# bird_beaks_2_0.net
KiCad netlist of a schematic drawn in EAGLE
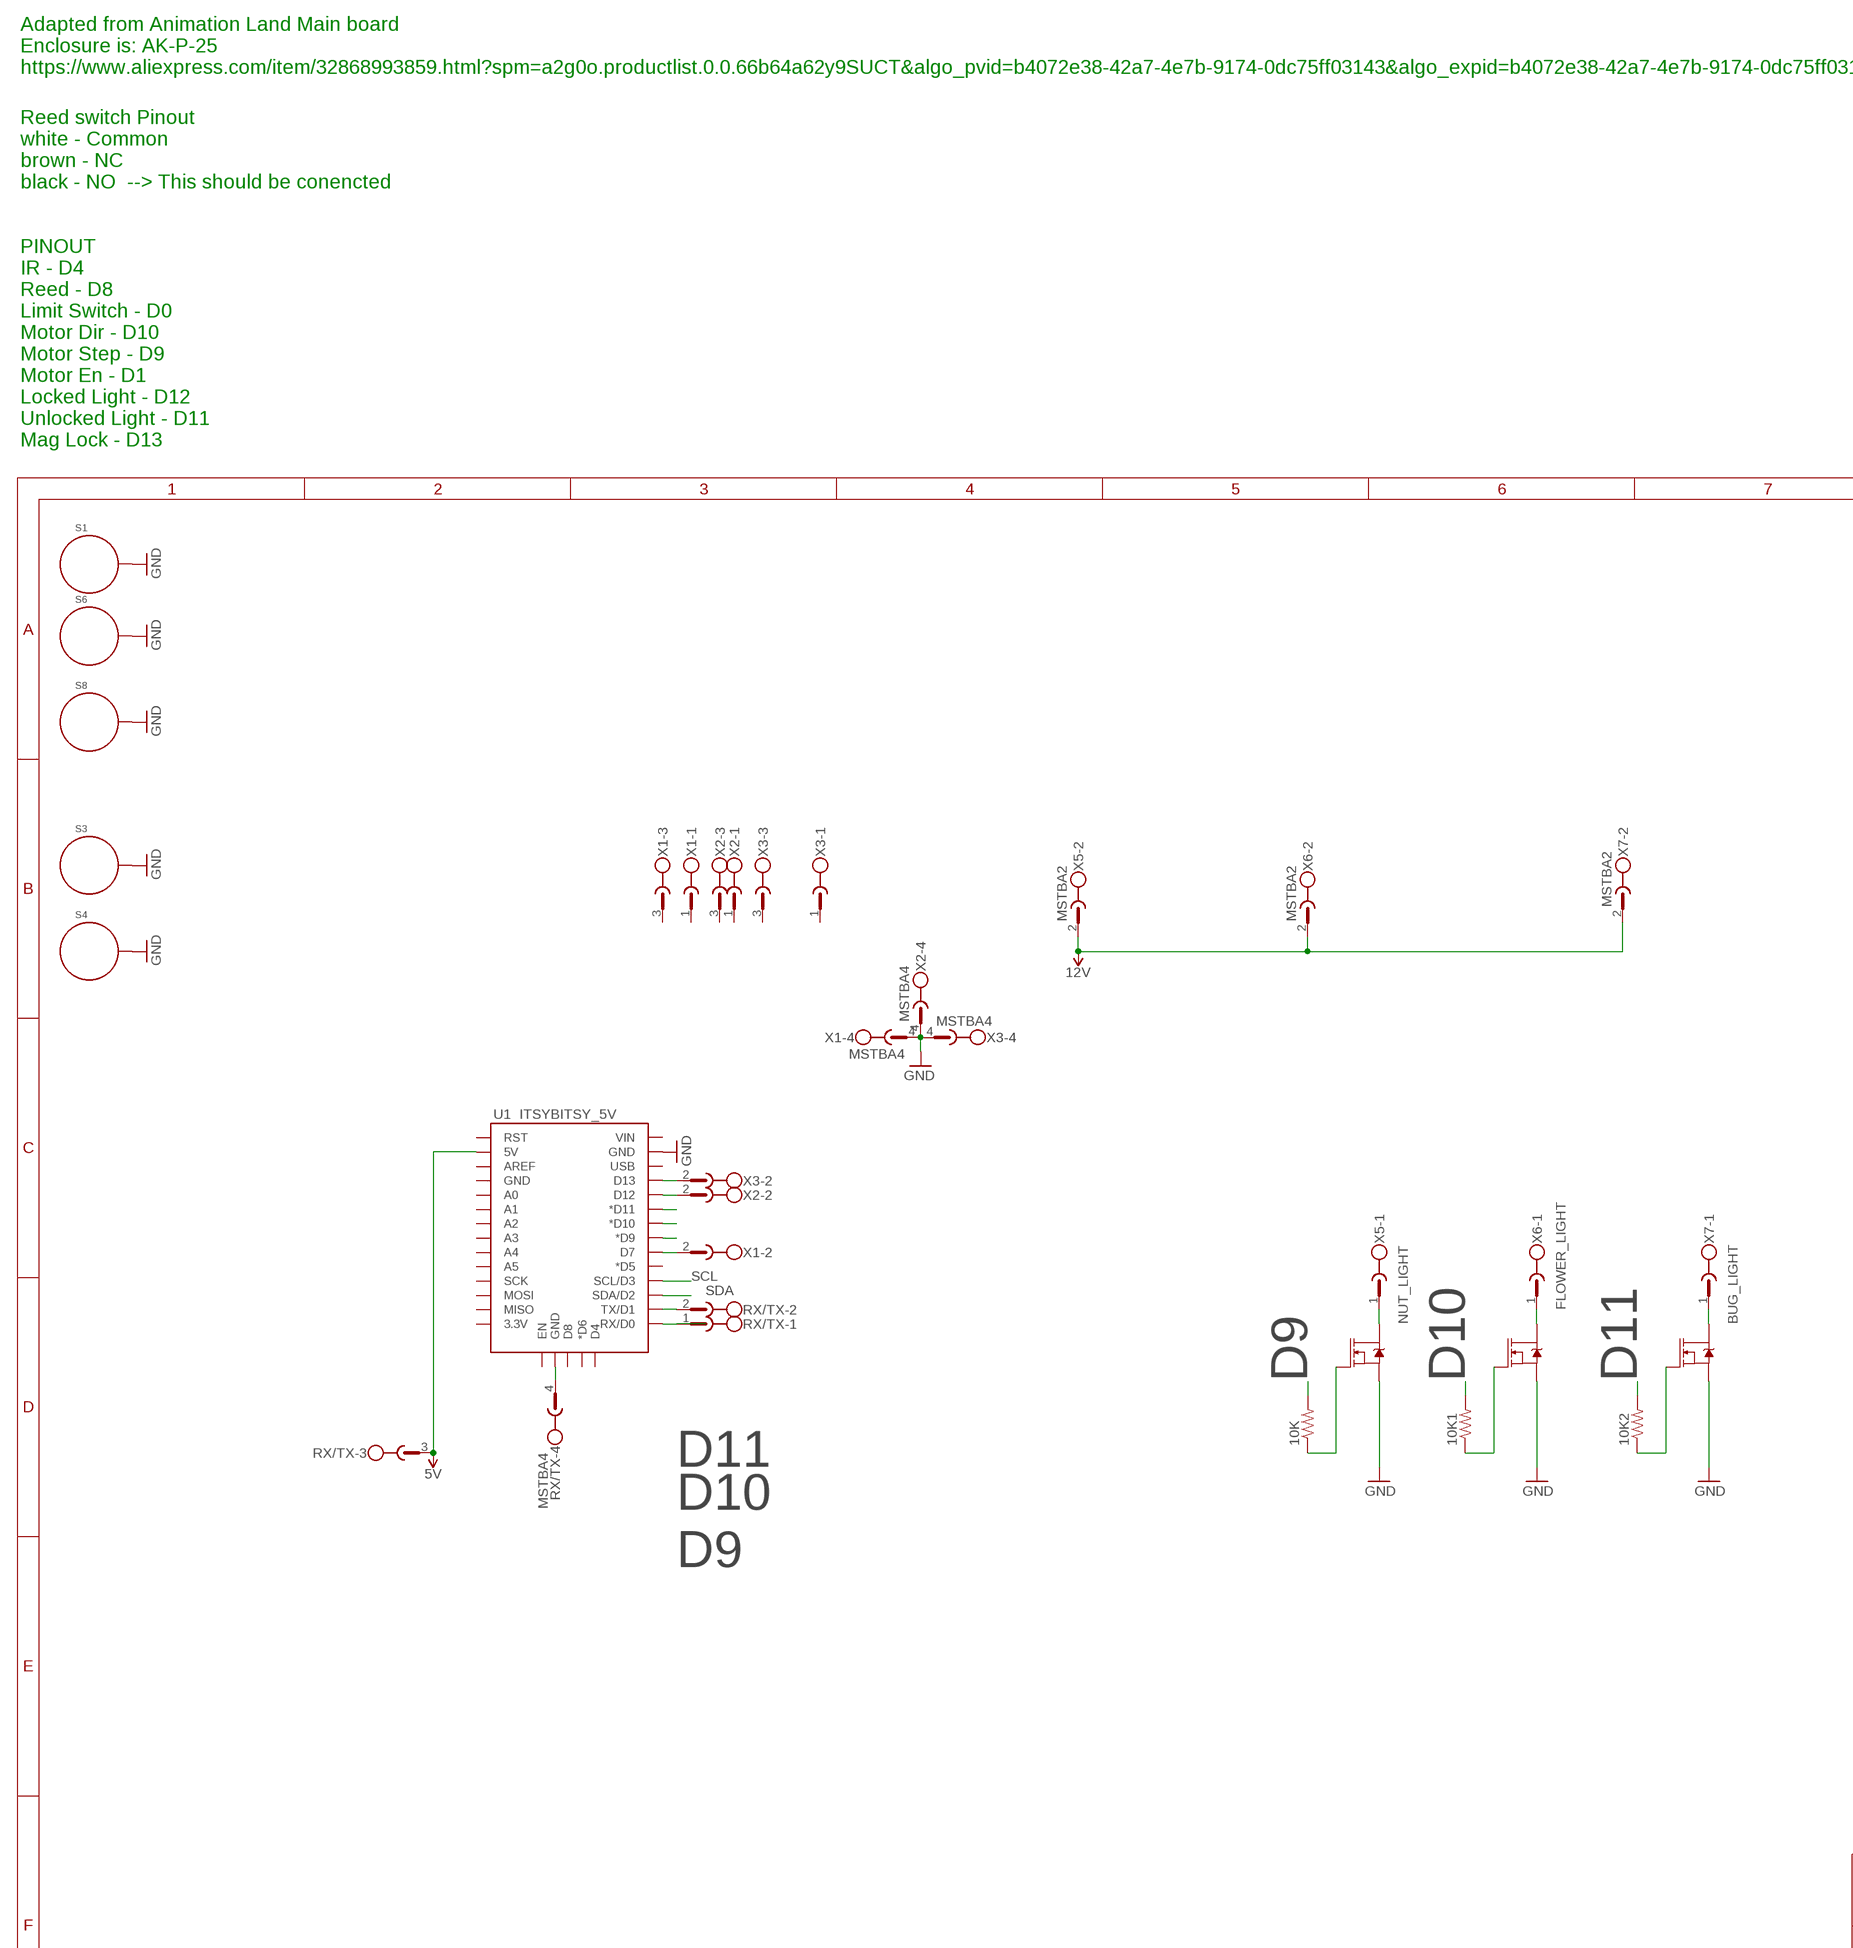
[diagram p0: schematic, sheet 1, part 1 of 2]
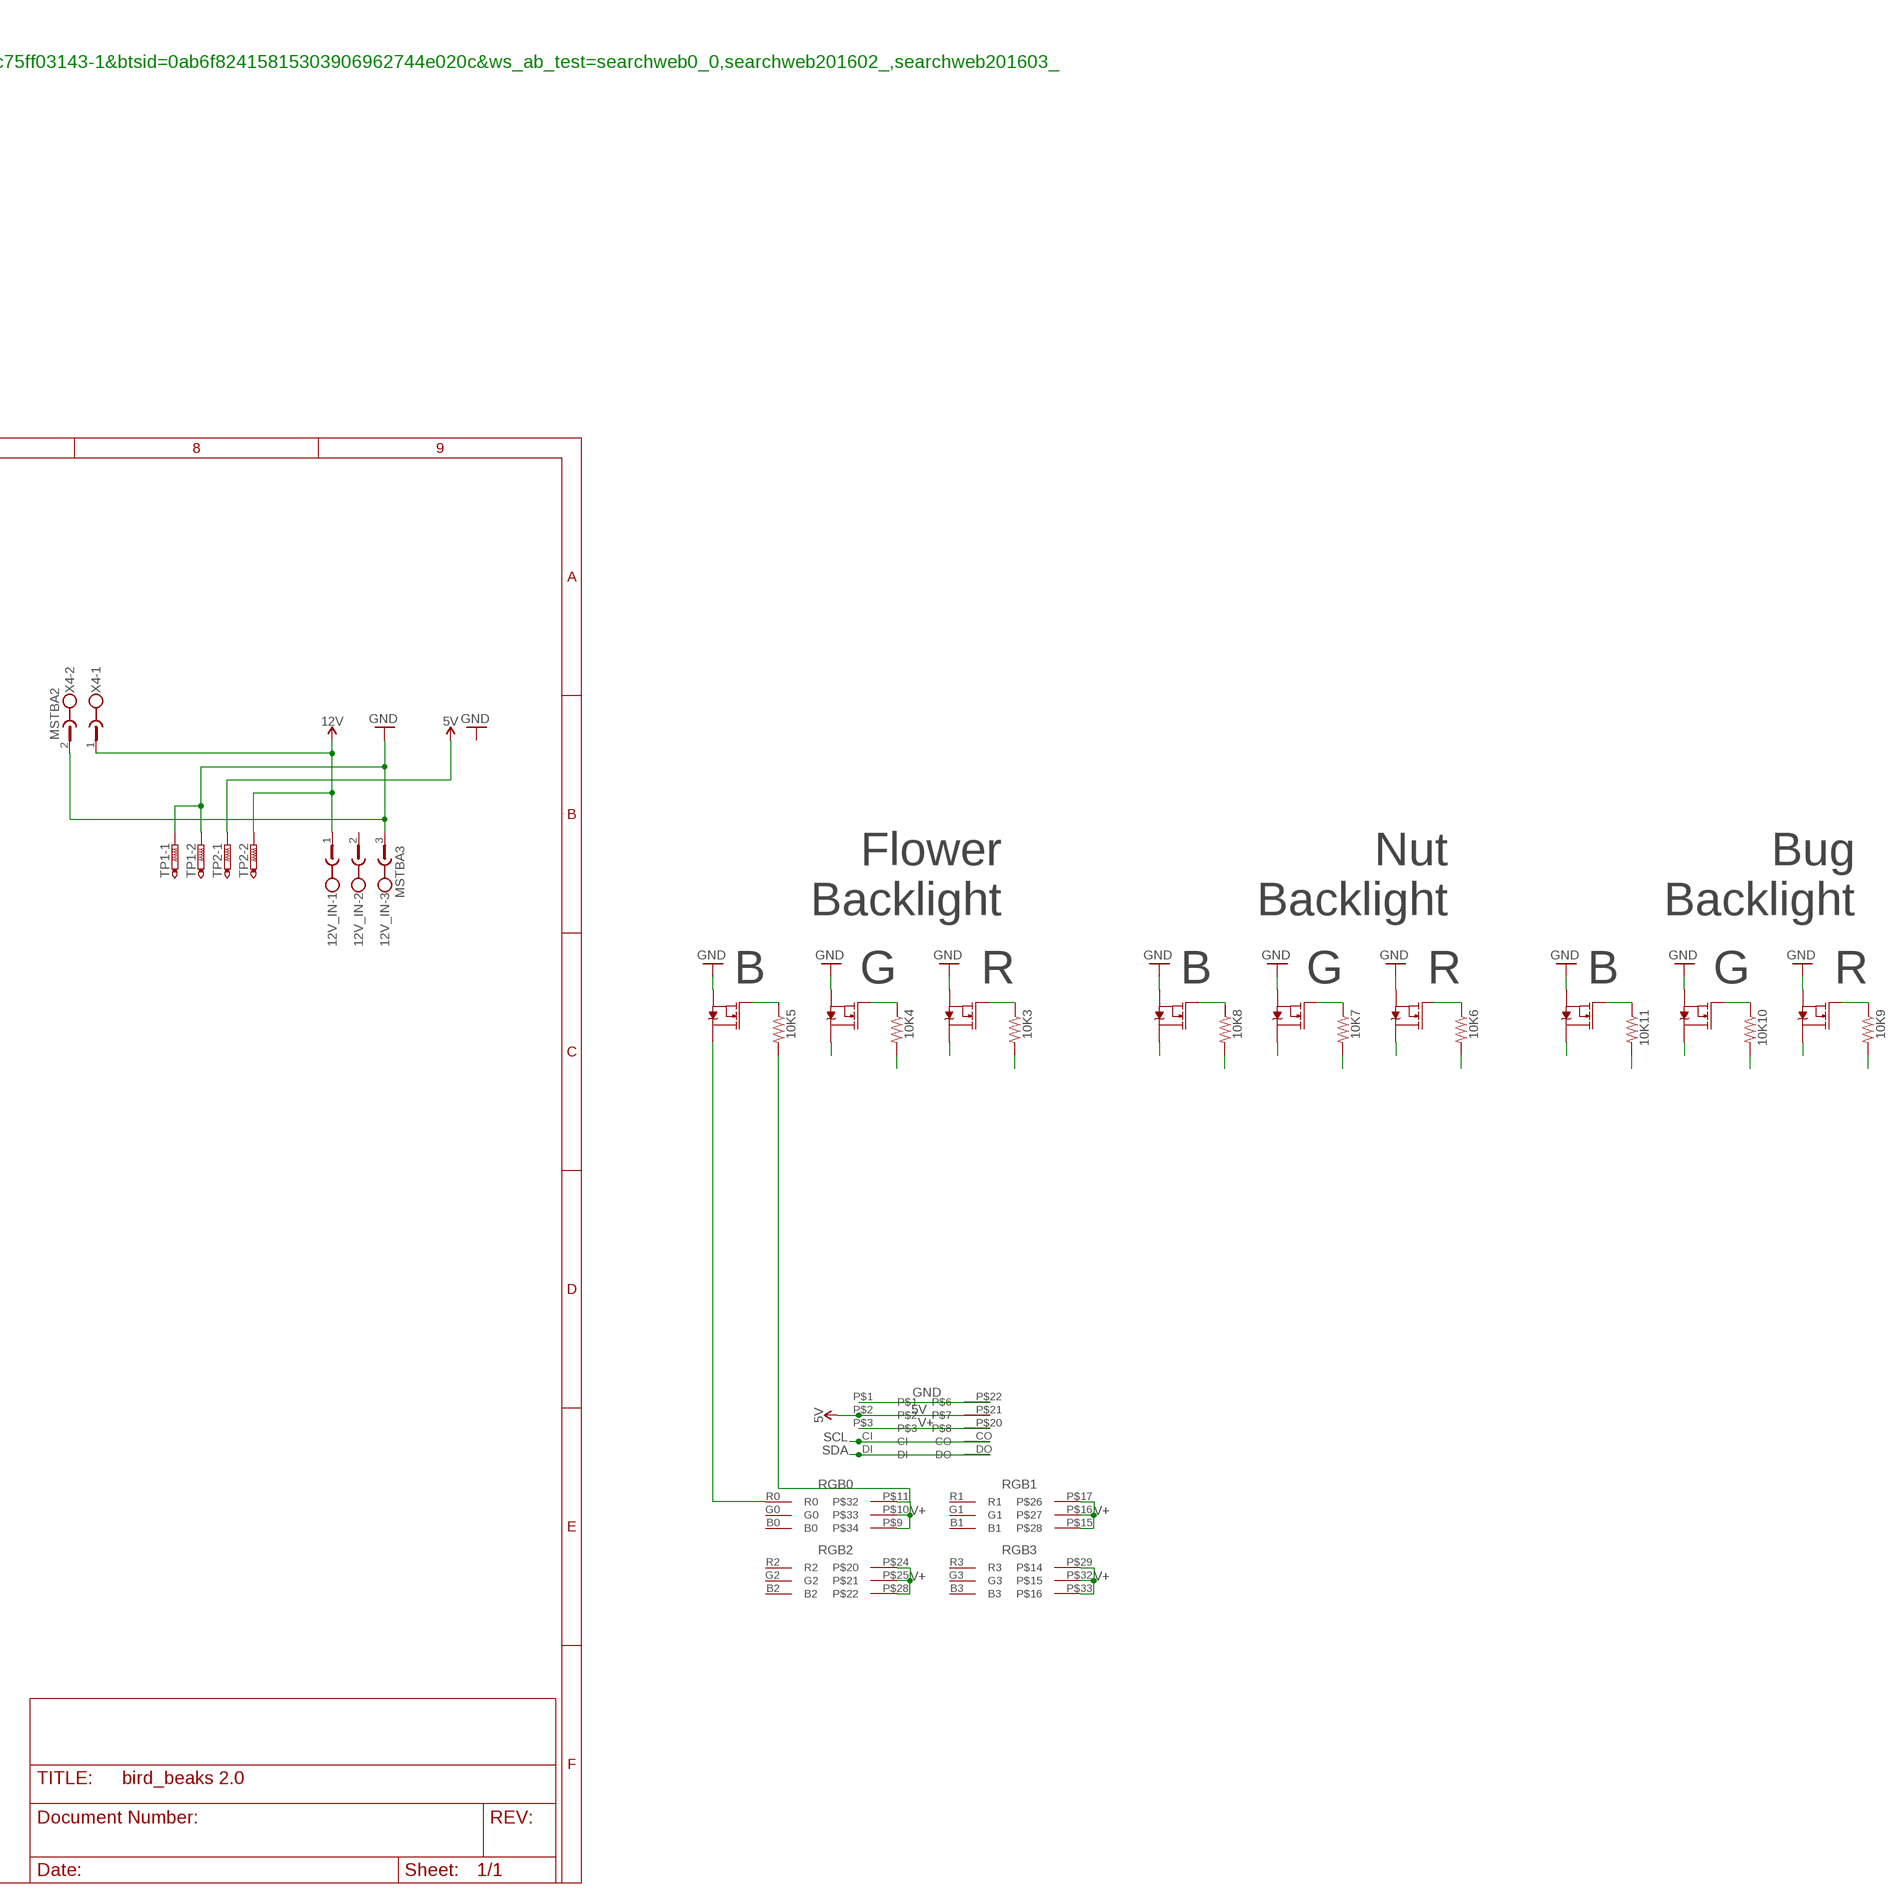
[diagram p1: schematic, sheet 1, part 2 of 2]

(export (version "E")
  (design (tool "Eeschema 10.0.6"))
  (components
    (comp (ref "10K")
      (value "R-US_M0805")
      (footprint "eagle-import:M0805")
      (libsource (lib "eagle-import") (part "R-US_M0805"))
    )
    (comp (ref "10K1")
      (value "R-US_M0805")
      (footprint "eagle-import:M0805")
      (libsource (lib "eagle-import") (part "R-US_M0805"))
    )
    (comp (ref "10K2")
      (value "R-US_M0805")
      (footprint "eagle-import:M0805")
      (libsource (lib "eagle-import") (part "R-US_M0805"))
    )
    (comp (ref "10K3")
      (value "R-US_M0805")
      (footprint "eagle-import:M0805")
      (libsource (lib "eagle-import") (part "R-US_M0805"))
    )
    (comp (ref "10K4")
      (value "R-US_M0805")
      (footprint "eagle-import:M0805")
      (libsource (lib "eagle-import") (part "R-US_M0805"))
    )
    (comp (ref "10K5")
      (value "R-US_M0805")
      (footprint "eagle-import:M0805")
      (libsource (lib "eagle-import") (part "R-US_M0805"))
    )
    (comp (ref "10K6")
      (value "R-US_M0805")
      (footprint "eagle-import:M0805")
      (libsource (lib "eagle-import") (part "R-US_M0805"))
    )
    (comp (ref "10K7")
      (value "R-US_M0805")
      (footprint "eagle-import:M0805")
      (libsource (lib "eagle-import") (part "R-US_M0805"))
    )
    (comp (ref "10K8")
      (value "R-US_M0805")
      (footprint "eagle-import:M0805")
      (libsource (lib "eagle-import") (part "R-US_M0805"))
    )
    (comp (ref "10K9")
      (value "R-US_M0805")
      (footprint "eagle-import:M0805")
      (libsource (lib "eagle-import") (part "R-US_M0805"))
    )
    (comp (ref "10K10")
      (value "R-US_M0805")
      (footprint "eagle-import:M0805")
      (libsource (lib "eagle-import") (part "R-US_M0805"))
    )
    (comp (ref "10K11")
      (value "R-US_M0805")
      (footprint "eagle-import:M0805")
      (libsource (lib "eagle-import") (part "R-US_M0805"))
    )
    (comp (ref "12V_IN")
      (value "MSTBA3")
      (footprint "eagle-import:MSTBA3")
      (fields (field (name "MF") "FARNELL") (field (name "MPN") "1757255"))
      (libsource (lib "eagle-import") (part "MSTBA3"))
    )
    (comp (ref "Q1")
      (value "MOSFET-NCH")
      (footprint "eagle-import:SO-8_POWER_PAK")
      (libsource (lib "eagle-import") (part "MOSFET-NCH"))
    )
    (comp (ref "Q2")
      (value "MOSFET-NCH")
      (footprint "eagle-import:SO-8_POWER_PAK")
      (libsource (lib "eagle-import") (part "MOSFET-NCH"))
    )
    (comp (ref "Q3")
      (value "MOSFET-NCH")
      (footprint "eagle-import:SO-8_POWER_PAK")
      (libsource (lib "eagle-import") (part "MOSFET-NCH"))
    )
    (comp (ref "Q4")
      (value "MOSFET-NCH")
      (footprint "eagle-import:SO-8_POWER_PAK")
      (libsource (lib "eagle-import") (part "MOSFET-NCH"))
    )
    (comp (ref "Q5")
      (value "MOSFET-NCH")
      (footprint "eagle-import:SO-8_POWER_PAK")
      (libsource (lib "eagle-import") (part "MOSFET-NCH"))
    )
    (comp (ref "Q6")
      (value "MOSFET-NCH")
      (footprint "eagle-import:SO-8_POWER_PAK")
      (libsource (lib "eagle-import") (part "MOSFET-NCH"))
    )
    (comp (ref "Q7")
      (value "MOSFET-NCH")
      (footprint "eagle-import:SO-8_POWER_PAK")
      (libsource (lib "eagle-import") (part "MOSFET-NCH"))
    )
    (comp (ref "Q8")
      (value "MOSFET-NCH")
      (footprint "eagle-import:SO-8_POWER_PAK")
      (libsource (lib "eagle-import") (part "MOSFET-NCH"))
    )
    (comp (ref "Q9")
      (value "MOSFET-NCH")
      (footprint "eagle-import:SO-8_POWER_PAK")
      (libsource (lib "eagle-import") (part "MOSFET-NCH"))
    )
    (comp (ref "Q10")
      (value "MOSFET-NCH")
      (footprint "eagle-import:SO-8_POWER_PAK")
      (libsource (lib "eagle-import") (part "MOSFET-NCH"))
    )
    (comp (ref "Q11")
      (value "MOSFET-NCH")
      (footprint "eagle-import:SO-8_POWER_PAK")
      (libsource (lib "eagle-import") (part "MOSFET-NCH"))
    )
    (comp (ref "Q12")
      (value "MOSFET-NCH")
      (footprint "eagle-import:SO-8_POWER_PAK")
      (libsource (lib "eagle-import") (part "MOSFET-NCH"))
    )
    (comp (ref "RX/TX")
      (value "MSTBA4")
      (footprint "eagle-import:MSTBA4")
      (fields (field (name "MF") "FARNELL") (field (name "MPN") "1757268"))
      (libsource (lib "eagle-import") (part "th_libraries_26281734_MSTBA4"))
    )
    (comp (ref "S1")
      (value "STANDOFF_ELECTRICAL5-32")
      (footprint "eagle-import:STANDOFF_ELECTRICAL_5_32")
      (libsource (lib "eagle-import") (part "STANDOFF_ELECTRICAL5-32"))
    )
    (comp (ref "S3")
      (value "STANDOFF_ELECTRICAL5-32")
      (footprint "eagle-import:STANDOFF_ELECTRICAL_5_32")
      (libsource (lib "eagle-import") (part "STANDOFF_ELECTRICAL5-32"))
    )
    (comp (ref "S4")
      (value "STANDOFF_ELECTRICAL5-32")
      (footprint "eagle-import:STANDOFF_ELECTRICAL_5_32")
      (libsource (lib "eagle-import") (part "STANDOFF_ELECTRICAL5-32"))
    )
    (comp (ref "S6")
      (value "STANDOFF_ELECTRICAL5-32")
      (footprint "eagle-import:STANDOFF_ELECTRICAL_5_32")
      (libsource (lib "eagle-import") (part "STANDOFF_ELECTRICAL5-32"))
    )
    (comp (ref "S8")
      (value "STANDOFF_ELECTRICAL5-32")
      (footprint "eagle-import:STANDOFF_ELECTRICAL_5_32")
      (libsource (lib "eagle-import") (part "STANDOFF_ELECTRICAL5-32"))
    )
    (comp (ref "TP1")
      (value "PTR2")
      (footprint "eagle-import:P2-38-17")
      (libsource (lib "eagle-import") (part "PTR2"))
    )
    (comp (ref "TP2")
      (value "PTR2")
      (footprint "eagle-import:P2-38-17")
      (libsource (lib "eagle-import") (part "PTR2"))
    )
    (comp (ref "U$1")
      (value "TLC59711")
      (footprint "eagle-import:ADAFRUIT_TLC59711")
      (libsource (lib "eagle-import") (part "TLC59711"))
    )
    (comp (ref "U1")
      (value "ITSYBITSY_5V")
      (footprint "eagle-import:ADAFRUIT_LENOARDO")
      (libsource (lib "eagle-import") (part "ITSYBITSY_5V"))
    )
    (comp (ref "X1")
      (value "MSTBA4")
      (footprint "eagle-import:MSTBA4")
      (fields (field (name "MF") "FARNELL") (field (name "MPN") "1757268"))
      (libsource (lib "eagle-import") (part "MSTBA4"))
    )
    (comp (ref "X2")
      (value "MSTBA4")
      (footprint "eagle-import:MSTBA4")
      (fields (field (name "MF") "FARNELL") (field (name "MPN") "1757268"))
      (libsource (lib "eagle-import") (part "MSTBA4"))
    )
    (comp (ref "X3")
      (value "MSTBA4")
      (footprint "eagle-import:MSTBA4")
      (fields (field (name "MF") "FARNELL") (field (name "MPN") "1757268"))
      (libsource (lib "eagle-import") (part "MSTBA4"))
    )
    (comp (ref "X4")
      (value "MSTBA2")
      (footprint "eagle-import:MSTBA2")
      (fields (field (name "MF") "FARNELL") (field (name "MPN") "1757242"))
      (libsource (lib "eagle-import") (part "MSTBA2"))
    )
    (comp (ref "X5")
      (value "MSTBA2")
      (footprint "eagle-import:MSTBA2")
      (fields (field (name "MF") "FARNELL") (field (name "MPN") "1757242"))
      (libsource (lib "eagle-import") (part "MSTBA2"))
    )
    (comp (ref "X6")
      (value "MSTBA2")
      (footprint "eagle-import:MSTBA2")
      (fields (field (name "MF") "FARNELL") (field (name "MPN") "1757242"))
      (libsource (lib "eagle-import") (part "MSTBA2"))
    )
    (comp (ref "X7")
      (value "MSTBA2")
      (footprint "eagle-import:MSTBA2")
      (fields (field (name "MF") "FARNELL") (field (name "MPN") "1757242"))
      (libsource (lib "eagle-import") (part "MSTBA2"))
    )
  )
  (nets
    (net (code "1") (name "/BUG_LIGHT") (class "Default")
      (node (ref "Q3") (pin "D1") (pinfunction "D_D1") (pintype "bidirectional"))
      (node (ref "X7") (pin "1") (pinfunction "1_1") (pintype "passive"))
    )
    (net (code "2") (name "/D9") (class "Default")
      (node (ref "10K") (pin "2") (pinfunction "2_2") (pintype "passive"))
      (node (ref "U1") (pin "D9") (pinfunction "*D9_D9") (pintype "bidirectional"))
    )
    (net (code "3") (name "/D10") (class "Default")
      (node (ref "10K1") (pin "2") (pinfunction "2_2") (pintype "passive"))
      (node (ref "U1") (pin "D10") (pinfunction "*D10_D10") (pintype "bidirectional"))
    )
    (net (code "4") (name "/D11") (class "Default")
      (node (ref "10K2") (pin "2") (pinfunction "2_2") (pintype "passive"))
      (node (ref "U1") (pin "D11") (pinfunction "*D11_D11") (pintype "bidirectional"))
    )
    (net (code "5") (name "/FLOWER_LIGHT") (class "Default")
      (node (ref "Q2") (pin "D1") (pinfunction "D_D1") (pintype "bidirectional"))
      (node (ref "X6") (pin "1") (pinfunction "1_1") (pintype "passive"))
    )
    (net (code "6") (name "/NUT_LIGHT") (class "Default")
      (node (ref "Q1") (pin "D1") (pinfunction "D_D1") (pintype "bidirectional"))
      (node (ref "X5") (pin "1") (pinfunction "1_1") (pintype "passive"))
    )
    (net (code "7") (name "/SCL") (class "Default")
      (node (ref "U$1") (pin "CI") (pinfunction "CI_CI") (pintype "bidirectional"))
      (node (ref "U$1") (pin "CO") (pinfunction "CO_CO") (pintype "bidirectional"))
      (node (ref "U1") (pin "SCL") (pinfunction "SCL/D3_SCL") (pintype "bidirectional"))
    )
    (net (code "8") (name "/SDA") (class "Default")
      (node (ref "U$1") (pin "DI") (pinfunction "DI_DI") (pintype "bidirectional"))
      (node (ref "U$1") (pin "DO") (pinfunction "DO_DO") (pintype "bidirectional"))
      (node (ref "U1") (pin "SDA") (pinfunction "SDA/D2_SDA") (pintype "bidirectional"))
    )
    (net (code "9") (name "/V+") (class "Default")
      (node (ref "10K5") (pin "2") (pinfunction "2_2") (pintype "passive"))
      (node (ref "U$1") (pin "P$10") (pinfunction "P$33_P$10") (pintype "bidirectional"))
      (node (ref "U$1") (pin "P$11") (pinfunction "P$32_P$11") (pintype "bidirectional"))
      (node (ref "U$1") (pin "P$15") (pinfunction "P$28_P$15") (pintype "bidirectional"))
      (node (ref "U$1") (pin "P$16") (pinfunction "P$27_P$16") (pintype "bidirectional"))
      (node (ref "U$1") (pin "P$17") (pinfunction "P$26_P$17") (pintype "bidirectional"))
      (node (ref "U$1") (pin "P$20") (pinfunction "P$8_P$20") (pintype "bidirectional"))
      (node (ref "U$1") (pin "P$24") (pinfunction "P$20_P$24") (pintype "bidirectional"))
      (node (ref "U$1") (pin "P$25") (pinfunction "P$21_P$25") (pintype "bidirectional"))
      (node (ref "U$1") (pin "P$28") (pinfunction "P$22_P$28") (pintype "bidirectional"))
      (node (ref "U$1") (pin "P$29") (pinfunction "P$14_P$29") (pintype "bidirectional"))
      (node (ref "U$1") (pin "P$3") (pinfunction "P$3_P$3") (pintype "bidirectional"))
      (node (ref "U$1") (pin "P$32") (pinfunction "P$15_P$32") (pintype "bidirectional"))
      (node (ref "U$1") (pin "P$33") (pinfunction "P$16_P$33") (pintype "bidirectional"))
      (node (ref "U$1") (pin "P$9") (pinfunction "P$34_P$9") (pintype "bidirectional"))
    )
    (net (code "10") (name "5V") (class "Default")
      (node (ref "RX/TX") (pin "3") (pinfunction "1_3") (pintype "passive"))
      (node (ref "TP2") (pin "TP-1") (pinfunction "TP_TP-1") (pintype "input"))
      (node (ref "U$1") (pin "P$2") (pinfunction "P$2_P$2") (pintype "bidirectional"))
      (node (ref "U$1") (pin "P$21") (pinfunction "P$7_P$21") (pintype "bidirectional"))
      (node (ref "U1") (pin "5V") (pinfunction "5V_5V") (pintype "bidirectional"))
    )
    (net (code "11") (name "12V") (class "Default")
      (node (ref "12V_IN") (pin "1") (pinfunction "1_1") (pintype "passive"))
      (node (ref "TP2") (pin "TP-2") (pinfunction "TP_TP-2") (pintype "input"))
      (node (ref "X4") (pin "1") (pinfunction "1_1") (pintype "passive"))
      (node (ref "X5") (pin "2") (pinfunction "1_2") (pintype "passive"))
      (node (ref "X6") (pin "2") (pinfunction "1_2") (pintype "passive"))
      (node (ref "X7") (pin "2") (pinfunction "1_2") (pintype "passive"))
    )
    (net (code "12") (name "GND") (class "Default")
      (node (ref "12V_IN") (pin "3") (pinfunction "1_3") (pintype "passive"))
      (node (ref "Q1") (pin "S") (pinfunction "S_S") (pintype "bidirectional"))
      (node (ref "Q10") (pin "S") (pinfunction "S_S") (pintype "bidirectional"))
      (node (ref "Q11") (pin "S") (pinfunction "S_S") (pintype "bidirectional"))
      (node (ref "Q12") (pin "S") (pinfunction "S_S") (pintype "bidirectional"))
      (node (ref "Q2") (pin "S") (pinfunction "S_S") (pintype "bidirectional"))
      (node (ref "Q3") (pin "S") (pinfunction "S_S") (pintype "bidirectional"))
      (node (ref "Q4") (pin "S") (pinfunction "S_S") (pintype "bidirectional"))
      (node (ref "Q5") (pin "S") (pinfunction "S_S") (pintype "bidirectional"))
      (node (ref "Q6") (pin "S") (pinfunction "S_S") (pintype "bidirectional"))
      (node (ref "Q7") (pin "S") (pinfunction "S_S") (pintype "bidirectional"))
      (node (ref "Q8") (pin "S") (pinfunction "S_S") (pintype "bidirectional"))
      (node (ref "Q9") (pin "S") (pinfunction "S_S") (pintype "bidirectional"))
      (node (ref "S1") (pin "P1") (pinfunction "P$1_P1") (pintype "bidirectional"))
      (node (ref "S3") (pin "P1") (pinfunction "P$1_P1") (pintype "bidirectional"))
      (node (ref "S4") (pin "P1") (pinfunction "P$1_P1") (pintype "bidirectional"))
      (node (ref "S6") (pin "P1") (pinfunction "P$1_P1") (pintype "bidirectional"))
      (node (ref "S8") (pin "P1") (pinfunction "P$1_P1") (pintype "bidirectional"))
      (node (ref "TP1") (pin "TP-1") (pinfunction "TP_TP-1") (pintype "input"))
      (node (ref "TP1") (pin "TP-2") (pinfunction "TP_TP-2") (pintype "input"))
      (node (ref "U$1") (pin "P$1") (pinfunction "P$1_P$1") (pintype "bidirectional"))
      (node (ref "U$1") (pin "P$22") (pinfunction "P$6_P$22") (pintype "bidirectional"))
      (node (ref "U1") (pin "GND@2") (pinfunction "GND_GND@2") (pintype "bidirectional"))
      (node (ref "X1") (pin "4") (pinfunction "1_4") (pintype "passive"))
      (node (ref "X2") (pin "4") (pinfunction "1_4") (pintype "passive"))
      (node (ref "X3") (pin "4") (pinfunction "1_4") (pintype "passive"))
      (node (ref "X4") (pin "2") (pinfunction "1_2") (pintype "passive"))
    )
    (net (code "13") (name "Net-(10K-Pad1)") (class "Default")
      (node (ref "10K") (pin "1") (pinfunction "1_1") (pintype "passive"))
      (node (ref "Q1") (pin "G") (pinfunction "G_G") (pintype "bidirectional"))
    )
    (net (code "14") (name "Net-(10K1-Pad1)") (class "Default")
      (node (ref "10K1") (pin "1") (pinfunction "1_1") (pintype "passive"))
      (node (ref "Q2") (pin "G") (pinfunction "G_G") (pintype "bidirectional"))
    )
    (net (code "15") (name "Net-(10K2-Pad1)") (class "Default")
      (node (ref "10K2") (pin "1") (pinfunction "1_1") (pintype "passive"))
      (node (ref "Q3") (pin "G") (pinfunction "G_G") (pintype "bidirectional"))
    )
    (net (code "16") (name "Net-(10K3-Pad1)") (class "Default")
      (node (ref "10K3") (pin "1") (pinfunction "1_1") (pintype "passive"))
      (node (ref "Q4") (pin "G") (pinfunction "G_G") (pintype "bidirectional"))
    )
    (net (code "17") (name "Net-(10K4-Pad1)") (class "Default")
      (node (ref "10K4") (pin "1") (pinfunction "1_1") (pintype "passive"))
      (node (ref "Q5") (pin "G") (pinfunction "G_G") (pintype "bidirectional"))
    )
    (net (code "18") (name "Net-(10K5-Pad1)") (class "Default")
      (node (ref "10K5") (pin "1") (pinfunction "1_1") (pintype "passive"))
      (node (ref "Q6") (pin "G") (pinfunction "G_G") (pintype "bidirectional"))
    )
    (net (code "19") (name "Net-(10K6-Pad1)") (class "Default")
      (node (ref "10K6") (pin "1") (pinfunction "1_1") (pintype "passive"))
      (node (ref "Q7") (pin "G") (pinfunction "G_G") (pintype "bidirectional"))
    )
    (net (code "20") (name "Net-(10K7-Pad1)") (class "Default")
      (node (ref "10K7") (pin "1") (pinfunction "1_1") (pintype "passive"))
      (node (ref "Q8") (pin "G") (pinfunction "G_G") (pintype "bidirectional"))
    )
    (net (code "21") (name "Net-(10K8-Pad1)") (class "Default")
      (node (ref "10K8") (pin "1") (pinfunction "1_1") (pintype "passive"))
      (node (ref "Q9") (pin "G") (pinfunction "G_G") (pintype "bidirectional"))
    )
    (net (code "22") (name "Net-(10K9-Pad1)") (class "Default")
      (node (ref "10K9") (pin "1") (pinfunction "1_1") (pintype "passive"))
      (node (ref "Q10") (pin "G") (pinfunction "G_G") (pintype "bidirectional"))
    )
    (net (code "23") (name "Net-(10K10-Pad1)") (class "Default")
      (node (ref "10K10") (pin "1") (pinfunction "1_1") (pintype "passive"))
      (node (ref "Q11") (pin "G") (pinfunction "G_G") (pintype "bidirectional"))
    )
    (net (code "24") (name "Net-(10K11-Pad1)") (class "Default")
      (node (ref "10K11") (pin "1") (pinfunction "1_1") (pintype "passive"))
      (node (ref "Q12") (pin "G") (pinfunction "G_G") (pintype "bidirectional"))
    )
    (net (code "25") (name "Net-(Q6-D)") (class "Default")
      (node (ref "Q6") (pin "D1") (pinfunction "D_D1") (pintype "bidirectional"))
      (node (ref "U$1") (pin "R0") (pinfunction "R0_R0") (pintype "bidirectional"))
    )
    (net (code "26") (name "Net-(RX/TXB-1)") (class "Default")
      (node (ref "RX/TX") (pin "2") (pinfunction "1_2") (pintype "passive"))
      (node (ref "U1") (pin "TX") (pinfunction "TX/D1_TX") (pintype "bidirectional"))
    )
    (net (code "27") (name "Net-(RX/TXD-1)") (class "Default")
      (node (ref "RX/TX") (pin "4") (pinfunction "1_4") (pintype "passive"))
      (node (ref "U1") (pin "GND@1") (pinfunction "GND_GND@1") (pintype "bidirectional"))
    )
    (net (code "28") (name "Net-(U1-RX{slash}D0)") (class "Default")
      (node (ref "RX/TX") (pin "1") (pinfunction "1_1") (pintype "passive"))
      (node (ref "U1") (pin "RX") (pinfunction "RX/D0_RX") (pintype "bidirectional"))
    )
    (net (code "29") (name "Net-(X1B-1)") (class "Default")
      (node (ref "U1") (pin "D7") (pinfunction "D7_D7") (pintype "bidirectional"))
      (node (ref "X1") (pin "2") (pinfunction "1_2") (pintype "passive"))
    )
    (net (code "30") (name "Net-(X2B-1)") (class "Default")
      (node (ref "U1") (pin "D12") (pinfunction "D12_D12") (pintype "bidirectional"))
      (node (ref "X2") (pin "2") (pinfunction "1_2") (pintype "passive"))
    )
    (net (code "31") (name "Net-(X3B-1)") (class "Default")
      (node (ref "U1") (pin "D13") (pinfunction "D13_D13") (pintype "bidirectional"))
      (node (ref "X3") (pin "2") (pinfunction "1_2") (pintype "passive"))
    )
    (net (code "32") (name "unconnected-(10K3-Pad2)") (class "Default")
      (node (ref "10K3") (pin "2") (pinfunction "2_2") (pintype "passive"))
    )
    (net (code "33") (name "unconnected-(10K4-Pad2)") (class "Default")
      (node (ref "10K4") (pin "2") (pinfunction "2_2") (pintype "passive"))
    )
    (net (code "34") (name "unconnected-(10K6-Pad2)") (class "Default")
      (node (ref "10K6") (pin "2") (pinfunction "2_2") (pintype "passive"))
    )
    (net (code "35") (name "unconnected-(10K7-Pad2)") (class "Default")
      (node (ref "10K7") (pin "2") (pinfunction "2_2") (pintype "passive"))
    )
    (net (code "36") (name "unconnected-(10K8-Pad2)") (class "Default")
      (node (ref "10K8") (pin "2") (pinfunction "2_2") (pintype "passive"))
    )
    (net (code "37") (name "unconnected-(10K9-Pad2)") (class "Default")
      (node (ref "10K9") (pin "2") (pinfunction "2_2") (pintype "passive"))
    )
    (net (code "38") (name "unconnected-(10K10-Pad2)") (class "Default")
      (node (ref "10K10") (pin "2") (pinfunction "2_2") (pintype "passive"))
    )
    (net (code "39") (name "unconnected-(10K11-Pad2)") (class "Default")
      (node (ref "10K11") (pin "2") (pinfunction "2_2") (pintype "passive"))
    )
    (net (code "40") (name "unconnected-(12V_INB-1-Pad2)") (class "Default")
      (node (ref "12V_IN") (pin "2") (pinfunction "1_2") (pintype "passive"))
    )
    (net (code "41") (name "unconnected-(Q4-D-PadD1)") (class "Default")
      (node (ref "Q4") (pin "D1") (pinfunction "D_D1") (pintype "bidirectional"))
    )
    (net (code "42") (name "unconnected-(Q5-D-PadD1)") (class "Default")
      (node (ref "Q5") (pin "D1") (pinfunction "D_D1") (pintype "bidirectional"))
    )
    (net (code "43") (name "unconnected-(Q7-D-PadD1)") (class "Default")
      (node (ref "Q7") (pin "D1") (pinfunction "D_D1") (pintype "bidirectional"))
    )
    (net (code "44") (name "unconnected-(Q8-D-PadD1)") (class "Default")
      (node (ref "Q8") (pin "D1") (pinfunction "D_D1") (pintype "bidirectional"))
    )
    (net (code "45") (name "unconnected-(Q9-D-PadD1)") (class "Default")
      (node (ref "Q9") (pin "D1") (pinfunction "D_D1") (pintype "bidirectional"))
    )
    (net (code "46") (name "unconnected-(Q10-D-PadD1)") (class "Default")
      (node (ref "Q10") (pin "D1") (pinfunction "D_D1") (pintype "bidirectional"))
    )
    (net (code "47") (name "unconnected-(Q11-D-PadD1)") (class "Default")
      (node (ref "Q11") (pin "D1") (pinfunction "D_D1") (pintype "bidirectional"))
    )
    (net (code "48") (name "unconnected-(Q12-D-PadD1)") (class "Default")
      (node (ref "Q12") (pin "D1") (pinfunction "D_D1") (pintype "bidirectional"))
    )
    (net (code "49") (name "unconnected-(U$1-PadB0)") (class "Default")
      (node (ref "U$1") (pin "B0") (pinfunction "B0_B0") (pintype "bidirectional"))
    )
    (net (code "50") (name "unconnected-(U$1-PadB1)") (class "Default")
      (node (ref "U$1") (pin "B1") (pinfunction "B1_B1") (pintype "bidirectional"))
    )
    (net (code "51") (name "unconnected-(U$1-PadB2)") (class "Default")
      (node (ref "U$1") (pin "B2") (pinfunction "B2_B2") (pintype "bidirectional"))
    )
    (net (code "52") (name "unconnected-(U$1-PadB3)") (class "Default")
      (node (ref "U$1") (pin "B3") (pinfunction "B3_B3") (pintype "bidirectional"))
    )
    (net (code "53") (name "unconnected-(U$1-PadG0)") (class "Default")
      (node (ref "U$1") (pin "G0") (pinfunction "G0_G0") (pintype "bidirectional"))
    )
    (net (code "54") (name "unconnected-(U$1-PadG1)") (class "Default")
      (node (ref "U$1") (pin "G1") (pinfunction "G1_G1") (pintype "bidirectional"))
    )
    (net (code "55") (name "unconnected-(U$1-PadG2)") (class "Default")
      (node (ref "U$1") (pin "G2") (pinfunction "G2_G2") (pintype "bidirectional"))
    )
    (net (code "56") (name "unconnected-(U$1-PadG3)") (class "Default")
      (node (ref "U$1") (pin "G3") (pinfunction "G3_G3") (pintype "bidirectional"))
    )
    (net (code "57") (name "unconnected-(U$1-PadR1)") (class "Default")
      (node (ref "U$1") (pin "R1") (pinfunction "R1_R1") (pintype "bidirectional"))
    )
    (net (code "58") (name "unconnected-(U$1-PadR2)") (class "Default")
      (node (ref "U$1") (pin "R2") (pinfunction "R2_R2") (pintype "bidirectional"))
    )
    (net (code "59") (name "unconnected-(U$1-PadR3)") (class "Default")
      (node (ref "U$1") (pin "R3") (pinfunction "R3_R3") (pintype "bidirectional"))
    )
    (net (code "60") (name "unconnected-(U1-*D5-PadD5)") (class "Default")
      (node (ref "U1") (pin "D5") (pinfunction "*D5_D5") (pintype "bidirectional"))
    )
    (net (code "61") (name "unconnected-(U1-*D6-PadD6)") (class "Default")
      (node (ref "U1") (pin "D6") (pinfunction "*D6_D6") (pintype "bidirectional"))
    )
    (net (code "62") (name "unconnected-(U1-3.3V-Pad3V)") (class "Default")
      (node (ref "U1") (pin "3V") (pinfunction "3.3V_3V") (pintype "bidirectional"))
    )
    (net (code "63") (name "unconnected-(U1-GND-PadGND@0)") (class "Default")
      (node (ref "U1") (pin "GND@0") (pinfunction "GND_GND@0") (pintype "bidirectional"))
    )
    (net (code "64") (name "unconnected-(U1-PadA0)") (class "Default")
      (node (ref "U1") (pin "A0") (pinfunction "A0_A0") (pintype "bidirectional"))
    )
    (net (code "65") (name "unconnected-(U1-PadA1)") (class "Default")
      (node (ref "U1") (pin "A1") (pinfunction "A1_A1") (pintype "bidirectional"))
    )
    (net (code "66") (name "unconnected-(U1-PadA2)") (class "Default")
      (node (ref "U1") (pin "A2") (pinfunction "A2_A2") (pintype "bidirectional"))
    )
    (net (code "67") (name "unconnected-(U1-PadA3)") (class "Default")
      (node (ref "U1") (pin "A3") (pinfunction "A3_A3") (pintype "bidirectional"))
    )
    (net (code "68") (name "unconnected-(U1-PadA4)") (class "Default")
      (node (ref "U1") (pin "A4") (pinfunction "A4_A4") (pintype "bidirectional"))
    )
    (net (code "69") (name "unconnected-(U1-PadA5)") (class "Default")
      (node (ref "U1") (pin "A5") (pinfunction "A5_A5") (pintype "bidirectional"))
    )
    (net (code "70") (name "unconnected-(U1-PadAREF)") (class "Default")
      (node (ref "U1") (pin "AREF") (pinfunction "AREF_AREF") (pintype "bidirectional"))
    )
    (net (code "71") (name "unconnected-(U1-PadD4)") (class "Default")
      (node (ref "U1") (pin "D4") (pinfunction "D4_D4") (pintype "bidirectional"))
    )
    (net (code "72") (name "unconnected-(U1-PadD8)") (class "Default")
      (node (ref "U1") (pin "D8") (pinfunction "D8_D8") (pintype "bidirectional"))
    )
    (net (code "73") (name "unconnected-(U1-PadEN)") (class "Default")
      (node (ref "U1") (pin "EN") (pinfunction "EN_EN") (pintype "bidirectional"))
    )
    (net (code "74") (name "unconnected-(U1-PadMISO)") (class "Default")
      (node (ref "U1") (pin "MISO") (pinfunction "MISO_MISO") (pintype "bidirectional"))
    )
    (net (code "75") (name "unconnected-(U1-PadMOSI)") (class "Default")
      (node (ref "U1") (pin "MOSI") (pinfunction "MOSI_MOSI") (pintype "bidirectional"))
    )
    (net (code "76") (name "unconnected-(U1-PadSCK)") (class "Default")
      (node (ref "U1") (pin "SCK") (pinfunction "SCK_SCK") (pintype "bidirectional"))
    )
    (net (code "77") (name "unconnected-(U1-PadUSB)") (class "Default")
      (node (ref "U1") (pin "USB") (pinfunction "USB_USB") (pintype "bidirectional"))
    )
    (net (code "78") (name "unconnected-(U1-PadVIN)") (class "Default")
      (node (ref "U1") (pin "VIN") (pinfunction "VIN_VIN") (pintype "bidirectional"))
    )
    (net (code "79") (name "unconnected-(U1-RST-PadRES)") (class "Default")
      (node (ref "U1") (pin "RES") (pinfunction "RST_RES") (pintype "bidirectional"))
    )
    (net (code "80") (name "unconnected-(X1-Pad1)") (class "Default")
      (node (ref "X1") (pin "1") (pinfunction "1_1") (pintype "passive"))
    )
    (net (code "81") (name "unconnected-(X1C-1-Pad3)") (class "Default")
      (node (ref "X1") (pin "3") (pinfunction "1_3") (pintype "passive"))
    )
    (net (code "82") (name "unconnected-(X2-Pad1)") (class "Default")
      (node (ref "X2") (pin "1") (pinfunction "1_1") (pintype "passive"))
    )
    (net (code "83") (name "unconnected-(X2C-1-Pad3)") (class "Default")
      (node (ref "X2") (pin "3") (pinfunction "1_3") (pintype "passive"))
    )
    (net (code "84") (name "unconnected-(X3-Pad1)") (class "Default")
      (node (ref "X3") (pin "1") (pinfunction "1_1") (pintype "passive"))
    )
    (net (code "85") (name "unconnected-(X3C-1-Pad3)") (class "Default")
      (node (ref "X3") (pin "3") (pinfunction "1_3") (pintype "passive"))
    )
  )
)
